# Power.net
KiCad netlist of a schematic drawn in Altium Designer
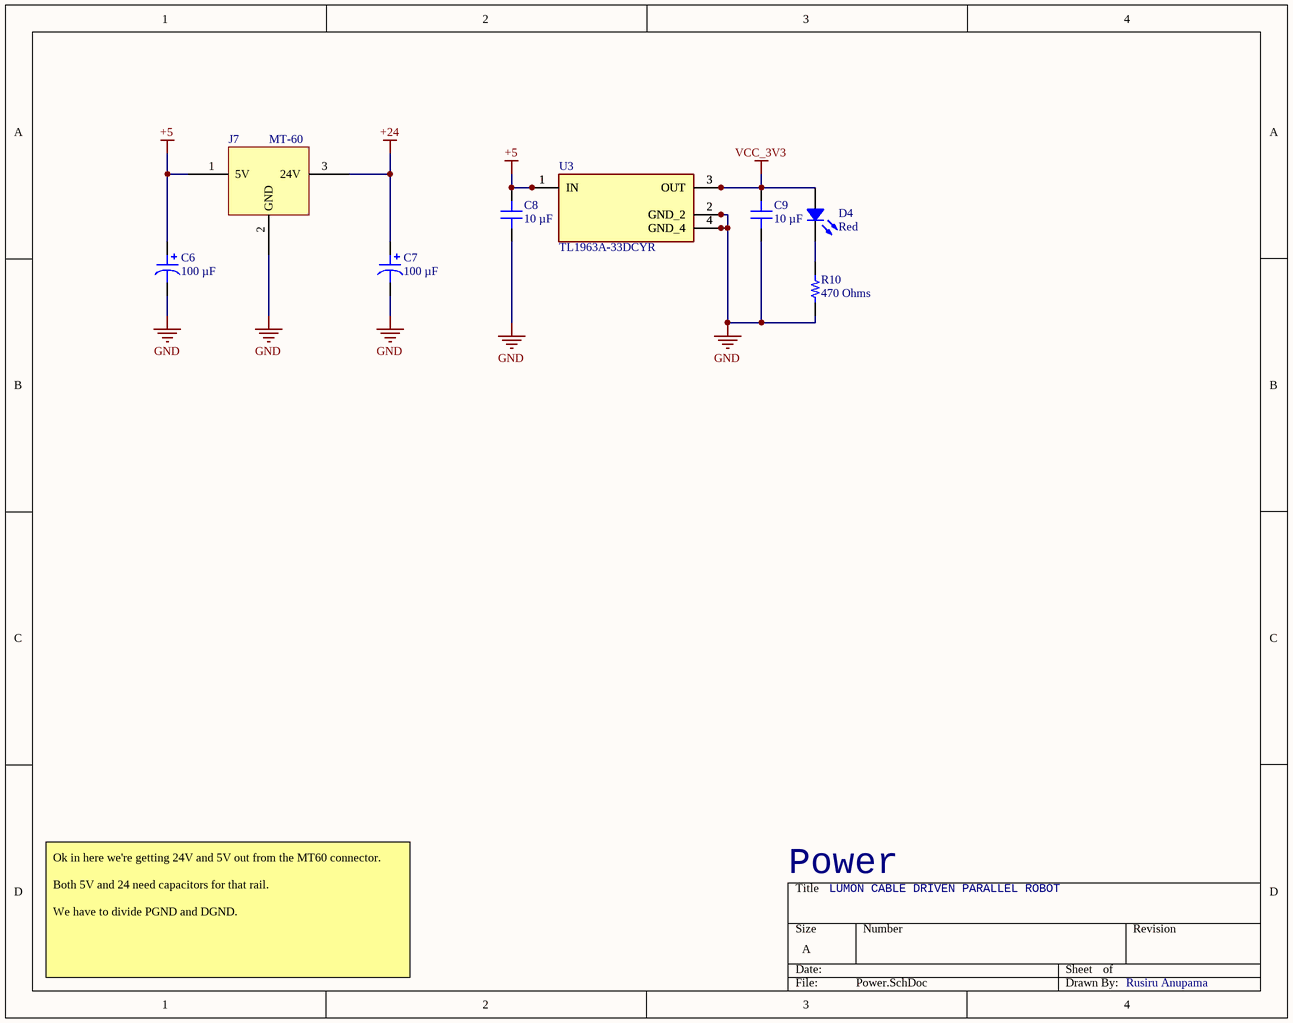
[diagram p0: Power.SchDoc]

(export (version "E")
  (design (tool "Eeschema 10.0.6"))
  (components
    (comp (ref "C6")
      (value "100 µF")
      (footprint "CAP ALSMD 8.3MM H10.5MM")
      (description "CAP ALUM 100UF 20% 50V SMD")
      (fields (field (name "PART NUMBER") "50SKV100M8X10.5") (field (name "MANUFACTURER") "Rubycon"))
      (libsource (lib "Celestial Altium Library - altium_library") (part "Polarised Capacitor"))
    )
    (comp (ref "C7")
      (value "100 µF")
      (footprint "CAP ALSMD 8.3MM H10.5MM")
      (description "CAP ALUM 100UF 20% 50V SMD")
      (fields (field (name "PART NUMBER") "50SKV100M8X10.5") (field (name "MANUFACTURER") "Rubycon"))
      (libsource (lib "Celestial Altium Library - altium_library") (part "Polarised Capacitor"))
    )
    (comp (ref "C8")
      (value "10 µF")
      (footprint "CAP 0805_2012")
      (description "CAP CER 10UF 10V X7S 0805")
      (fields
        (field (name "PART NUMBER") "CL21Y106KPQVPNE")
        (field (name "CAPACITANCE") "10 µF")
        (field (name "MANUFACTURER") "Samsung Electro-Mechanics")
      )
      (libsource (lib "Celestial Altium Library - altium_library") (part "Capacitor"))
    )
    (comp (ref "C9")
      (value "10 µF")
      (footprint "CAP 0805_2012")
      (description "CAP CER 10UF 10V X7S 0805")
      (fields
        (field (name "PART NUMBER") "CL21Y106KPQVPNE")
        (field (name "CAPACITANCE") "10 µF")
        (field (name "MANUFACTURER") "Samsung Electro-Mechanics")
      )
      (libsource (lib "Celestial Altium Library - altium_library") (part "Capacitor"))
    )
    (comp (ref "D4")
      (value "Red")
      (footprint "LED 0805_2012 RED")
      (description "LED RED 0805 SMD")
      (fields (field (name "PART NUMBER") "5990110007F") (field (name "MANUFACTURER") "Dialight"))
      (libsource (lib "Celestial Altium Library - altium_library") (part "LED"))
    )
    (comp (ref "J7")
      (value "MT-60")
      (footprint "MT-60")
      (fields (field (name "LCSC PART #") "C99176"))
      (libsource (lib "Actuator Lib") (part "MT-60"))
    )
    (comp (ref "R10")
      (value "470 Ohms")
      (footprint "RES 0805_2012")
      (description "RES SMD 470 OHM 0.1% 1/4W 0805")
      (fields
        (field (name "PART NUMBER") "ERJ-PB6B4700V")
        (field (name "MANUFACTURER") "Panasonic Electronic Components")
      )
      (libsource (lib "Celestial Altium Library - altium_library") (part "Resistor"))
    )
    (comp (ref "U3")
      (value "TL1963A-33DCYR")
      (footprint "VREG_TL1963A-33DCYR")
      (description "1.5-A, 20-V, low-dropout voltage regulator with reverse current & reverse voltage protection")
      (fields (field (name "MF") "Texas Instruments") (field (name "LCSC PART #") "C181262"))
      (libsource (lib "Actuator Lib") (part "TL1963A-33DCYR"))
    )
  )
  (nets
    (net (code "1") (name "+5") (class "Default")
      (node (ref "C6") (pin "1") (pinfunction "1_1") (pintype "passive"))
      (node (ref "C8") (pin "2") (pinfunction "2_2") (pintype "passive"))
      (node (ref "J7") (pin "1") (pinfunction "5V_1") (pintype "passive"))
      (node (ref "U3") (pin "1") (pinfunction "IN_1") (pintype "power_in"))
    )
    (net (code "2") (name "+24") (class "Default")
      (node (ref "C7") (pin "1") (pinfunction "1_1") (pintype "passive"))
      (node (ref "J7") (pin "3") (pinfunction "24V_3") (pintype "passive"))
    )
    (net (code "3") (name "GND") (class "Default")
      (node (ref "C6") (pin "2") (pinfunction "2_2") (pintype "passive"))
      (node (ref "C7") (pin "2") (pinfunction "2_2") (pintype "passive"))
      (node (ref "C8") (pin "1") (pinfunction "1_1") (pintype "passive"))
      (node (ref "C9") (pin "1") (pinfunction "1_1") (pintype "passive"))
      (node (ref "J7") (pin "2") (pinfunction "GND_2") (pintype "passive"))
      (node (ref "R10") (pin "1") (pinfunction "1_1") (pintype "passive"))
      (node (ref "U3") (pin "2") (pinfunction "GND_2_2") (pintype "power_in"))
      (node (ref "U3") (pin "4") (pinfunction "GND_4_4") (pintype "power_in"))
    )
    (net (code "4") (name "Net-(D4-Pad2)") (class "Default")
      (node (ref "D4") (pin "2") (pinfunction "2_2") (pintype "passive"))
      (node (ref "R10") (pin "2") (pinfunction "2_2") (pintype "passive"))
    )
    (net (code "5") (name "VCC_3V3") (class "Default")
      (node (ref "C9") (pin "2") (pinfunction "2_2") (pintype "passive"))
      (node (ref "D4") (pin "1") (pinfunction "1_1") (pintype "passive"))
      (node (ref "U3") (pin "3") (pinfunction "OUT_3") (pintype "power_in"))
    )
  )
)
